# STM32_RX.net
KiCad netlist of a schematic drawn in EAGLE
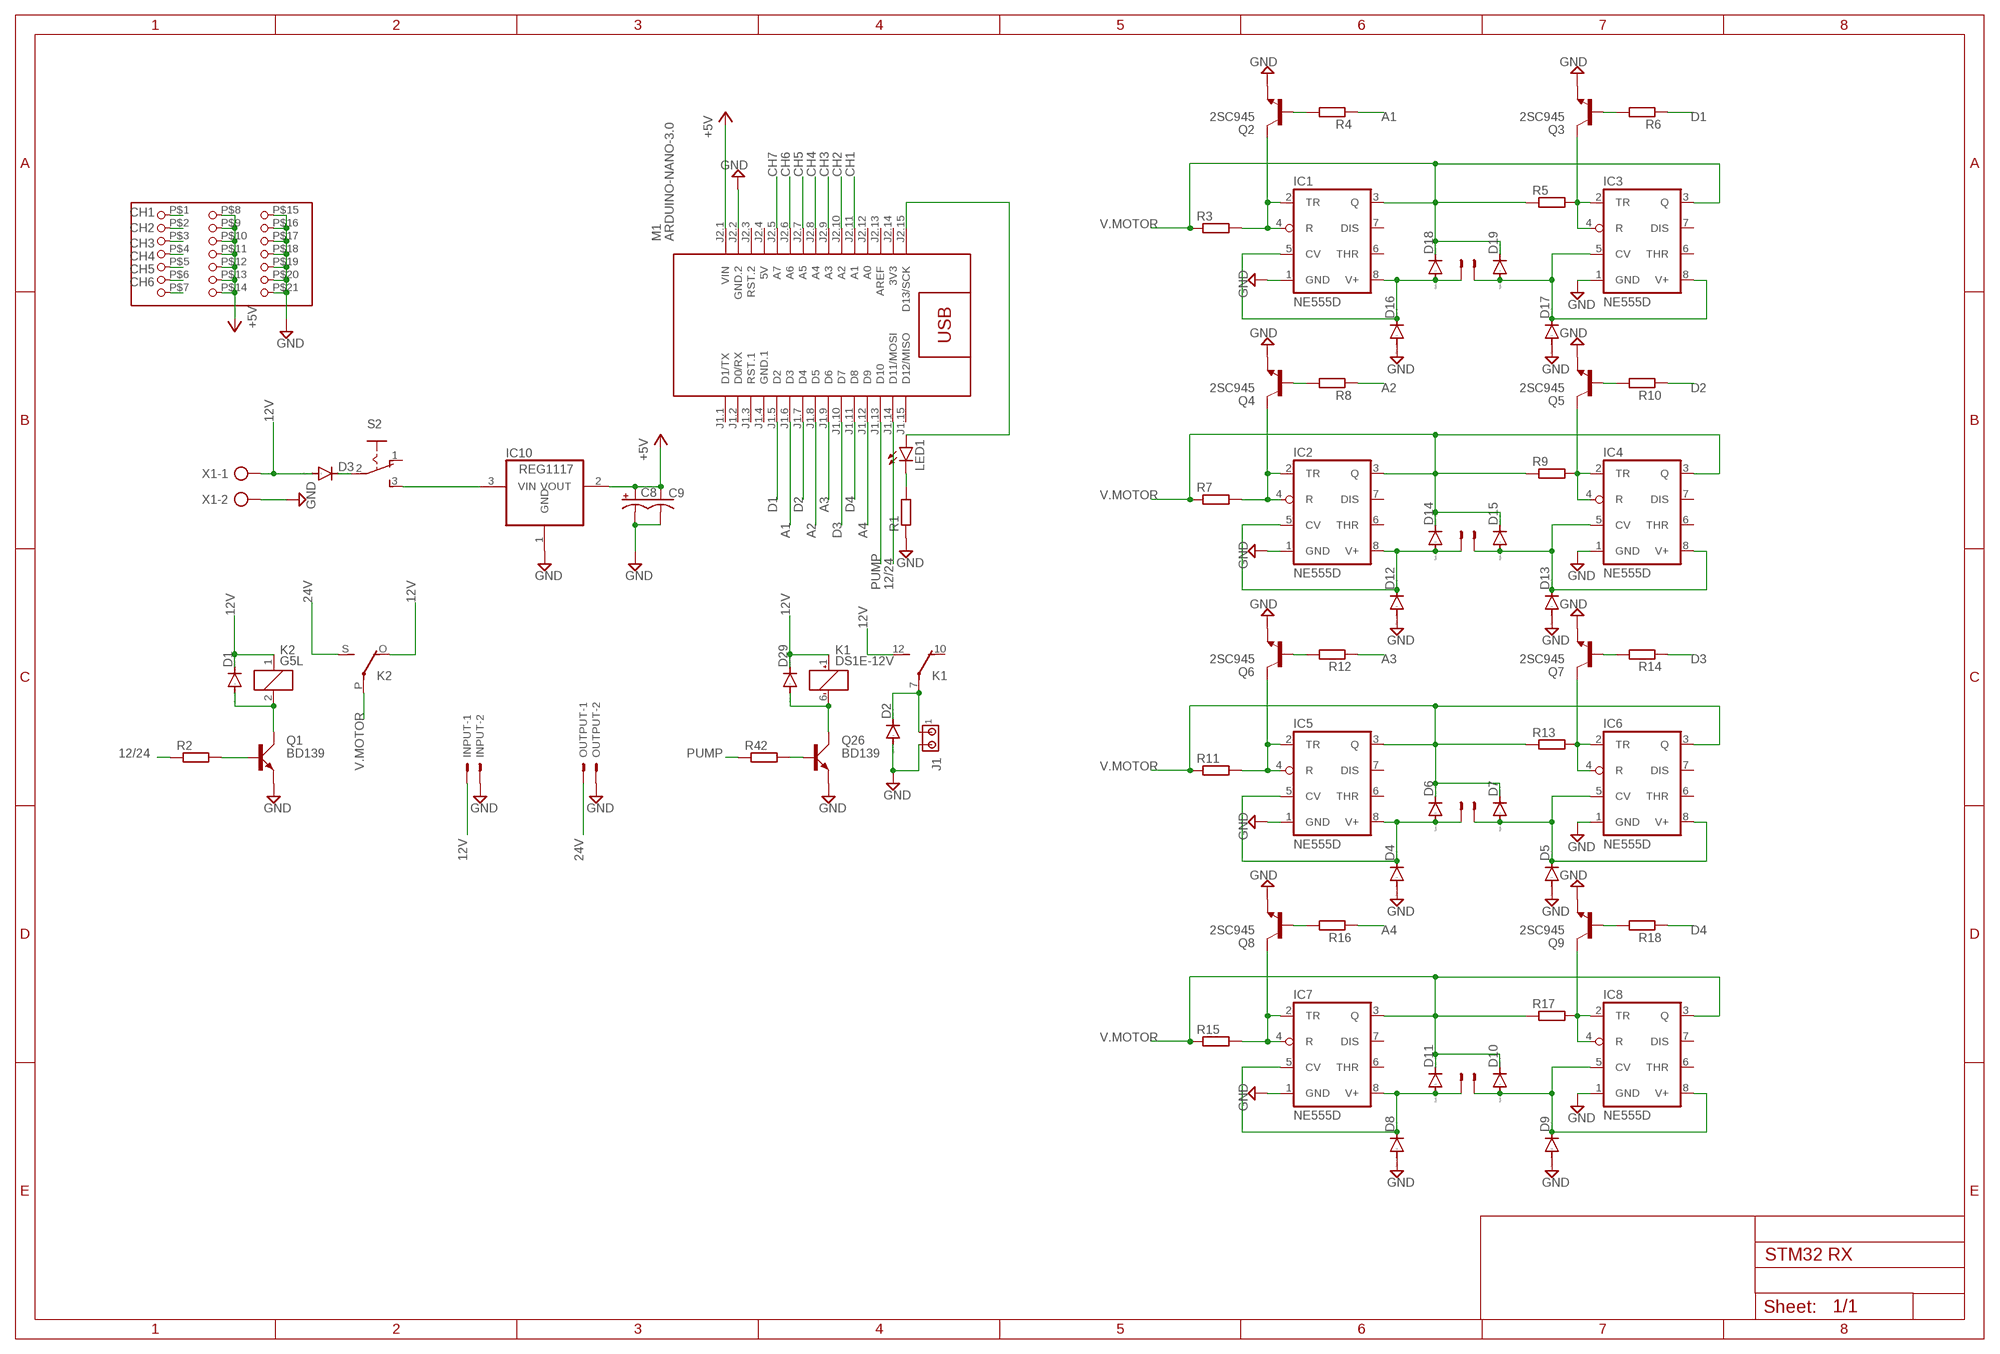
[diagram p0: schematic, sheet 1]

(export (version "E")
  (design (tool "Eeschema 10.0.6"))
  (components
    (comp (ref "C8")
      (value "CPOL-USE2.5-6")
      (footprint "eagle-import:E2,5-6")
      (libsource (lib "eagle-import") (part "CPOL-USE2.5-6"))
    )
    (comp (ref "C9")
      (value "C-US050-025X075")
      (footprint "eagle-import:C050-025X075")
      (libsource (lib "eagle-import") (part "C-US050-025X075"))
    )
    (comp (ref "D1")
      (value "1N4933")
      (footprint "eagle-import:DO41-10")
      (libsource (lib "eagle-import") (part "1N4933"))
    )
    (comp (ref "D2")
      (value "1N4933")
      (footprint "eagle-import:DO41-10")
      (libsource (lib "eagle-import") (part "1N4933"))
    )
    (comp (ref "D3")
      (value "1N4933")
      (footprint "eagle-import:DO41-10")
      (libsource (lib "eagle-import") (part "1N4933"))
    )
    (comp (ref "D4")
      (value "1N4933")
      (footprint "eagle-import:DO41-10")
      (libsource (lib "eagle-import") (part "1N4933"))
    )
    (comp (ref "D5")
      (value "1N4933")
      (footprint "eagle-import:DO41-10")
      (libsource (lib "eagle-import") (part "1N4933"))
    )
    (comp (ref "D6")
      (value "1N4933")
      (footprint "eagle-import:DO41-10")
      (libsource (lib "eagle-import") (part "1N4933"))
    )
    (comp (ref "D7")
      (value "1N4933")
      (footprint "eagle-import:DO41-10")
      (libsource (lib "eagle-import") (part "1N4933"))
    )
    (comp (ref "D8")
      (value "1N4933")
      (footprint "eagle-import:DO41-10")
      (libsource (lib "eagle-import") (part "1N4933"))
    )
    (comp (ref "D9")
      (value "1N4933")
      (footprint "eagle-import:DO41-10")
      (libsource (lib "eagle-import") (part "1N4933"))
    )
    (comp (ref "D10")
      (value "1N4933")
      (footprint "eagle-import:DO41-10")
      (libsource (lib "eagle-import") (part "1N4933"))
    )
    (comp (ref "D11")
      (value "1N4933")
      (footprint "eagle-import:DO41-10")
      (libsource (lib "eagle-import") (part "1N4933"))
    )
    (comp (ref "D12")
      (value "1N4933")
      (footprint "eagle-import:DO41-10")
      (libsource (lib "eagle-import") (part "1N4933"))
    )
    (comp (ref "D13")
      (value "1N4933")
      (footprint "eagle-import:DO41-10")
      (libsource (lib "eagle-import") (part "1N4933"))
    )
    (comp (ref "D14")
      (value "1N4933")
      (footprint "eagle-import:DO41-10")
      (libsource (lib "eagle-import") (part "1N4933"))
    )
    (comp (ref "D15")
      (value "1N4933")
      (footprint "eagle-import:DO41-10")
      (libsource (lib "eagle-import") (part "1N4933"))
    )
    (comp (ref "D16")
      (value "1N4933")
      (footprint "eagle-import:DO41-10")
      (libsource (lib "eagle-import") (part "1N4933"))
    )
    (comp (ref "D17")
      (value "1N4933")
      (footprint "eagle-import:DO41-10")
      (libsource (lib "eagle-import") (part "1N4933"))
    )
    (comp (ref "D18")
      (value "1N4933")
      (footprint "eagle-import:DO41-10")
      (libsource (lib "eagle-import") (part "1N4933"))
    )
    (comp (ref "D19")
      (value "1N4933")
      (footprint "eagle-import:DO41-10")
      (libsource (lib "eagle-import") (part "1N4933"))
    )
    (comp (ref "D29")
      (value "1N4933")
      (footprint "eagle-import:DO41-10")
      (libsource (lib "eagle-import") (part "1N4933"))
    )
    (comp (ref "IC1")
      (value "NE555D")
      (footprint "eagle-import:SO08")
      (libsource (lib "eagle-import") (part "555DNE"))
    )
    (comp (ref "IC2")
      (value "NE555D")
      (footprint "eagle-import:SO08")
      (libsource (lib "eagle-import") (part "555DNE"))
    )
    (comp (ref "IC3")
      (value "NE555D")
      (footprint "eagle-import:SO08")
      (libsource (lib "eagle-import") (part "555DNE"))
    )
    (comp (ref "IC4")
      (value "NE555D")
      (footprint "eagle-import:SO08")
      (libsource (lib "eagle-import") (part "555DNE"))
    )
    (comp (ref "IC5")
      (value "NE555D")
      (footprint "eagle-import:SO08")
      (libsource (lib "eagle-import") (part "555DNE"))
    )
    (comp (ref "IC6")
      (value "NE555D")
      (footprint "eagle-import:SO08")
      (libsource (lib "eagle-import") (part "555DNE"))
    )
    (comp (ref "IC7")
      (value "NE555D")
      (footprint "eagle-import:SO08")
      (libsource (lib "eagle-import") (part "555DNE"))
    )
    (comp (ref "IC8")
      (value "NE555D")
      (footprint "eagle-import:SO08")
      (libsource (lib "eagle-import") (part "555DNE"))
    )
    (comp (ref "IC10")
      (value "REG1117")
      (footprint "eagle-import:SOT223")
      (libsource (lib "eagle-import") (part "REG1117"))
    )
    (comp (ref "INPUT")
      (value "22-23-2021")
      (footprint "eagle-import:22-23-2021")
      (fields (field (name "MF") "MOLEX"))
      (libsource (lib "eagle-import") (part "22-23-2021"))
    )
    (comp (ref "J1")
      (value "MTA02-156")
      (footprint "eagle-import:1X2MTA")
      (libsource (lib "eagle-import") (part "MTA02-156"))
    )
    (comp (ref "K1")
      (value "DS1E-12V")
      (footprint "eagle-import:DS1E")
      (libsource (lib "eagle-import") (part "DS1E-?12V"))
    )
    (comp (ref "K2")
      (value "G5L")
      (footprint "eagle-import:G5LE")
      (libsource (lib "eagle-import") (part "G5L"))
    )
    (comp (ref "LED1")
      (value "LED5MM")
      (footprint "eagle-import:LED5MM")
      (libsource (lib "eagle-import") (part "LED5MM"))
    )
    (comp (ref "M1")
      (value "ARDUINO-NANO-3.0")
      (footprint "eagle-import:ARDUINO-NANO-3.0")
      (libsource (lib "eagle-import") (part "ARDUINO-NANO-3.0"))
    )
    (comp (ref "OUTPUT")
      (value "22-23-2021")
      (footprint "eagle-import:22-23-2021")
      (fields (field (name "MF") "MOLEX"))
      (libsource (lib "eagle-import") (part "22-23-2021"))
    )
    (comp (ref "OUTPUT1")
      (value "22-23-2021")
      (footprint "eagle-import:22-23-2021")
      (fields (field (name "MF") "MOLEX"))
      (libsource (lib "eagle-import") (part "22-23-2021"))
    )
    (comp (ref "OUTPUT2")
      (value "22-23-2021")
      (footprint "eagle-import:22-23-2021")
      (fields (field (name "MF") "MOLEX"))
      (libsource (lib "eagle-import") (part "22-23-2021"))
    )
    (comp (ref "OUTPUT3")
      (value "22-23-2021")
      (footprint "eagle-import:22-23-2021")
      (fields (field (name "MF") "MOLEX"))
      (libsource (lib "eagle-import") (part "22-23-2021"))
    )
    (comp (ref "OUTPUT4")
      (value "22-23-2021")
      (footprint "eagle-import:22-23-2021")
      (fields (field (name "MF") "MOLEX"))
      (libsource (lib "eagle-import") (part "22-23-2021"))
    )
    (comp (ref "Q1")
      (value "BD139")
      (footprint "eagle-import:TO126AV")
      (libsource (lib "eagle-import") (part "BD139"))
    )
    (comp (ref "Q2")
      (value "2SC945")
      (footprint "eagle-import:TO92-ECB")
      (libsource (lib "eagle-import") (part "2SC945"))
    )
    (comp (ref "Q3")
      (value "2SC945")
      (footprint "eagle-import:TO92-ECB")
      (libsource (lib "eagle-import") (part "2SC945"))
    )
    (comp (ref "Q4")
      (value "2SC945")
      (footprint "eagle-import:TO92-ECB")
      (libsource (lib "eagle-import") (part "2SC945"))
    )
    (comp (ref "Q5")
      (value "2SC945")
      (footprint "eagle-import:TO92-ECB")
      (libsource (lib "eagle-import") (part "2SC945"))
    )
    (comp (ref "Q6")
      (value "2SC945")
      (footprint "eagle-import:TO92-ECB")
      (libsource (lib "eagle-import") (part "2SC945"))
    )
    (comp (ref "Q7")
      (value "2SC945")
      (footprint "eagle-import:TO92-ECB")
      (libsource (lib "eagle-import") (part "2SC945"))
    )
    (comp (ref "Q8")
      (value "2SC945")
      (footprint "eagle-import:TO92-ECB")
      (libsource (lib "eagle-import") (part "2SC945"))
    )
    (comp (ref "Q9")
      (value "2SC945")
      (footprint "eagle-import:TO92-ECB")
      (libsource (lib "eagle-import") (part "2SC945"))
    )
    (comp (ref "Q26")
      (value "BD139")
      (footprint "eagle-import:TO126AV")
      (libsource (lib "eagle-import") (part "BD139"))
    )
    (comp (ref "R1")
      (value "R-EU_0207/10")
      (footprint "eagle-import:0207_10")
      (libsource (lib "eagle-import") (part "R-EU_0207/10"))
    )
    (comp (ref "R2")
      (value "R-EU_0207/10")
      (footprint "eagle-import:0207_10")
      (libsource (lib "eagle-import") (part "R-EU_0207/10"))
    )
    (comp (ref "R3")
      (value "R-EU_0207/10")
      (footprint "eagle-import:0207_10")
      (libsource (lib "eagle-import") (part "R-EU_0207/10"))
    )
    (comp (ref "R4")
      (value "R-EU_0207/10")
      (footprint "eagle-import:0207_10")
      (libsource (lib "eagle-import") (part "R-EU_0207/10"))
    )
    (comp (ref "R5")
      (value "R-EU_0207/10")
      (footprint "eagle-import:0207_10")
      (libsource (lib "eagle-import") (part "R-EU_0207/10"))
    )
    (comp (ref "R6")
      (value "R-EU_0207/10")
      (footprint "eagle-import:0207_10")
      (libsource (lib "eagle-import") (part "R-EU_0207/10"))
    )
    (comp (ref "R7")
      (value "R-EU_0207/10")
      (footprint "eagle-import:0207_10")
      (libsource (lib "eagle-import") (part "R-EU_0207/10"))
    )
    (comp (ref "R8")
      (value "R-EU_0207/10")
      (footprint "eagle-import:0207_10")
      (libsource (lib "eagle-import") (part "R-EU_0207/10"))
    )
    (comp (ref "R9")
      (value "R-EU_0207/10")
      (footprint "eagle-import:0207_10")
      (libsource (lib "eagle-import") (part "R-EU_0207/10"))
    )
    (comp (ref "R10")
      (value "R-EU_0207/10")
      (footprint "eagle-import:0207_10")
      (libsource (lib "eagle-import") (part "R-EU_0207/10"))
    )
    (comp (ref "R11")
      (value "R-EU_0207/10")
      (footprint "eagle-import:0207_10")
      (libsource (lib "eagle-import") (part "R-EU_0207/10"))
    )
    (comp (ref "R12")
      (value "R-EU_0207/10")
      (footprint "eagle-import:0207_10")
      (libsource (lib "eagle-import") (part "R-EU_0207/10"))
    )
    (comp (ref "R13")
      (value "R-EU_0207/10")
      (footprint "eagle-import:0207_10")
      (libsource (lib "eagle-import") (part "R-EU_0207/10"))
    )
    (comp (ref "R14")
      (value "R-EU_0207/10")
      (footprint "eagle-import:0207_10")
      (libsource (lib "eagle-import") (part "R-EU_0207/10"))
    )
    (comp (ref "R15")
      (value "R-EU_0207/10")
      (footprint "eagle-import:0207_10")
      (libsource (lib "eagle-import") (part "R-EU_0207/10"))
    )
    (comp (ref "R16")
      (value "R-EU_0207/10")
      (footprint "eagle-import:0207_10")
      (libsource (lib "eagle-import") (part "R-EU_0207/10"))
    )
    (comp (ref "R17")
      (value "R-EU_0207/10")
      (footprint "eagle-import:0207_10")
      (libsource (lib "eagle-import") (part "R-EU_0207/10"))
    )
    (comp (ref "R18")
      (value "R-EU_0207/10")
      (footprint "eagle-import:0207_10")
      (libsource (lib "eagle-import") (part "R-EU_0207/10"))
    )
    (comp (ref "R42")
      (value "R-EU_0207/10")
      (footprint "eagle-import:0207_10")
      (libsource (lib "eagle-import") (part "R-EU_0207/10"))
    )
    (comp (ref "S2")
      (value "255SB")
      (footprint "eagle-import:255SB")
      (libsource (lib "eagle-import") (part "255SB"))
    )
    (comp (ref "U$1")
      (value "PINHEAD3")
      (footprint "eagle-import:PINHEAD3")
      (libsource (lib "eagle-import") (part "PINHEAD3"))
    )
    (comp (ref "X1")
      (value "AK500/2")
      (footprint "eagle-import:AK500_2")
      (libsource (lib "eagle-import") (part "AK500/2"))
    )
  )
  (nets
    (net (code "1") (name "+5V") (class "Default")
      (node (ref "C8") (pin "+") (pinfunction "+_+") (pintype "passive"))
      (node (ref "C9") (pin "1") (pinfunction "1_1") (pintype "passive"))
      (node (ref "IC10") (pin "2") (pinfunction "VOUT_2") (pintype "output"))
      (node (ref "M1") (pin "J2.1") (pinfunction "VIN_J2.1") (pintype "power_in"))
      (node (ref "U$1") (pin "P$10") (pinfunction "P$10_P$10") (pintype "bidirectional"))
      (node (ref "U$1") (pin "P$11") (pinfunction "P$11_P$11") (pintype "bidirectional"))
      (node (ref "U$1") (pin "P$12") (pinfunction "P$12_P$12") (pintype "bidirectional"))
      (node (ref "U$1") (pin "P$13") (pinfunction "P$13_P$13") (pintype "bidirectional"))
      (node (ref "U$1") (pin "P$14") (pinfunction "P$14_P$14") (pintype "bidirectional"))
      (node (ref "U$1") (pin "P$8") (pinfunction "P$8_P$8") (pintype "bidirectional"))
      (node (ref "U$1") (pin "P$9") (pinfunction "P$9_P$9") (pintype "bidirectional"))
    )
    (net (code "2") (name "/3V3") (class "Default")
      (node (ref "M1") (pin "J2.14") (pinfunction "3V3_J2.14") (pintype "power_in"))
    )
    (net (code "3") (name "/5V") (class "Default")
      (node (ref "M1") (pin "J2.4") (pinfunction "5V_J2.4") (pintype "power_in"))
    )
    (net (code "4") (name "/12V") (class "Default")
      (node (ref "D1") (pin "C") (pinfunction "C_C") (pintype "passive"))
      (node (ref "D29") (pin "C") (pinfunction "C_C") (pintype "passive"))
      (node (ref "D3") (pin "A") (pinfunction "A_A") (pintype "passive"))
      (node (ref "INPUT") (pin "1") (pinfunction "S_1") (pintype "passive"))
      (node (ref "K1") (pin "1") (pinfunction "+_1") (pintype "passive"))
      (node (ref "K1") (pin "12") (pinfunction "S_12") (pintype "passive"))
      (node (ref "K2") (pin "1") (pinfunction "1_1") (pintype "passive"))
      (node (ref "K2") (pin "O") (pinfunction "O_O") (pintype "passive"))
      (node (ref "X1") (pin "1") (pinfunction "KL_1") (pintype "passive"))
    )
    (net (code "5") (name "/12{slash}24") (class "Default")
      (node (ref "M1") (pin "J1.14") (pinfunction "D11/MOSI_J1.14") (pintype "bidirectional"))
      (node (ref "R2") (pin "1") (pinfunction "1_1") (pintype "passive"))
    )
    (net (code "6") (name "/24V") (class "Default")
      (node (ref "K2") (pin "S") (pinfunction "S_S") (pintype "passive"))
      (node (ref "OUTPUT") (pin "1") (pinfunction "S_1") (pintype "passive"))
    )
    (net (code "7") (name "/A1") (class "Default")
      (node (ref "M1") (pin "J1.6") (pinfunction "D3_J1.6") (pintype "bidirectional"))
      (node (ref "R4") (pin "1") (pinfunction "1_1") (pintype "passive"))
    )
    (net (code "8") (name "/A2") (class "Default")
      (node (ref "M1") (pin "J1.8") (pinfunction "D5_J1.8") (pintype "bidirectional"))
      (node (ref "R8") (pin "1") (pinfunction "1_1") (pintype "passive"))
    )
    (net (code "9") (name "/A3") (class "Default")
      (node (ref "M1") (pin "J1.9") (pinfunction "D6_J1.9") (pintype "bidirectional"))
      (node (ref "R12") (pin "1") (pinfunction "1_1") (pintype "passive"))
    )
    (net (code "10") (name "/A4") (class "Default")
      (node (ref "M1") (pin "J1.12") (pinfunction "D9_J1.12") (pintype "bidirectional"))
      (node (ref "R16") (pin "1") (pinfunction "1_1") (pintype "passive"))
    )
    (net (code "11") (name "/CH1") (class "Default")
      (node (ref "M1") (pin "J2.11") (pinfunction "A1_J2.11") (pintype "bidirectional"))
      (node (ref "U$1") (pin "P$1") (pinfunction "P$1_P$1") (pintype "bidirectional"))
    )
    (net (code "12") (name "/CH2") (class "Default")
      (node (ref "M1") (pin "J2.10") (pinfunction "A2_J2.10") (pintype "bidirectional"))
      (node (ref "U$1") (pin "P$2") (pinfunction "P$2_P$2") (pintype "bidirectional"))
    )
    (net (code "13") (name "/CH3") (class "Default")
      (node (ref "M1") (pin "J2.9") (pinfunction "A3_J2.9") (pintype "bidirectional"))
      (node (ref "U$1") (pin "P$3") (pinfunction "P$3_P$3") (pintype "bidirectional"))
    )
    (net (code "14") (name "/CH4") (class "Default")
      (node (ref "M1") (pin "J2.8") (pinfunction "A4_J2.8") (pintype "bidirectional"))
      (node (ref "U$1") (pin "P$4") (pinfunction "P$4_P$4") (pintype "bidirectional"))
    )
    (net (code "15") (name "/CH5") (class "Default")
      (node (ref "M1") (pin "J2.7") (pinfunction "A5_J2.7") (pintype "bidirectional"))
      (node (ref "U$1") (pin "P$5") (pinfunction "P$5_P$5") (pintype "bidirectional"))
    )
    (net (code "16") (name "/CH6") (class "Default")
      (node (ref "M1") (pin "J2.6") (pinfunction "A6_J2.6") (pintype "bidirectional"))
      (node (ref "U$1") (pin "P$6") (pinfunction "P$6_P$6") (pintype "bidirectional"))
    )
    (net (code "17") (name "/CH7") (class "Default")
      (node (ref "M1") (pin "J2.5") (pinfunction "A7_J2.5") (pintype "bidirectional"))
    )
    (net (code "18") (name "/D1") (class "Default")
      (node (ref "M1") (pin "J1.5") (pinfunction "D2_J1.5") (pintype "bidirectional"))
      (node (ref "R6") (pin "1") (pinfunction "1_1") (pintype "passive"))
    )
    (net (code "19") (name "/D2") (class "Default")
      (node (ref "M1") (pin "J1.7") (pinfunction "D4_J1.7") (pintype "bidirectional"))
      (node (ref "R10") (pin "1") (pinfunction "1_1") (pintype "passive"))
    )
    (net (code "20") (name "/D3") (class "Default")
      (node (ref "M1") (pin "J1.10") (pinfunction "D7_J1.10") (pintype "bidirectional"))
      (node (ref "R14") (pin "1") (pinfunction "1_1") (pintype "passive"))
    )
    (net (code "21") (name "/D4") (class "Default")
      (node (ref "M1") (pin "J1.11") (pinfunction "D8_J1.11") (pintype "bidirectional"))
      (node (ref "R18") (pin "1") (pinfunction "1_1") (pintype "passive"))
    )
    (net (code "22") (name "/GND.1") (class "Default")
      (node (ref "M1") (pin "J1.4") (pinfunction "GND.1_J1.4") (pintype "power_in"))
    )
    (net (code "23") (name "/PUMP") (class "Default")
      (node (ref "M1") (pin "J1.13") (pinfunction "D10_J1.13") (pintype "bidirectional"))
      (node (ref "R42") (pin "1") (pinfunction "1_1") (pintype "passive"))
    )
    (net (code "24") (name "/V.MOTOR") (class "Default")
      (node (ref "D10") (pin "C") (pinfunction "C_C") (pintype "passive"))
      (node (ref "D11") (pin "C") (pinfunction "C_C") (pintype "passive"))
      (node (ref "D14") (pin "C") (pinfunction "C_C") (pintype "passive"))
      (node (ref "D15") (pin "C") (pinfunction "C_C") (pintype "passive"))
      (node (ref "D18") (pin "C") (pinfunction "C_C") (pintype "passive"))
      (node (ref "D19") (pin "C") (pinfunction "C_C") (pintype "passive"))
      (node (ref "D6") (pin "C") (pinfunction "C_C") (pintype "passive"))
      (node (ref "D7") (pin "C") (pinfunction "C_C") (pintype "passive"))
      (node (ref "IC1") (pin "3") (pinfunction "Q_3") (pintype "output"))
      (node (ref "IC2") (pin "3") (pinfunction "Q_3") (pintype "output"))
      (node (ref "IC3") (pin "3") (pinfunction "Q_3") (pintype "output"))
      (node (ref "IC4") (pin "3") (pinfunction "Q_3") (pintype "output"))
      (node (ref "IC5") (pin "3") (pinfunction "Q_3") (pintype "output"))
      (node (ref "IC6") (pin "3") (pinfunction "Q_3") (pintype "output"))
      (node (ref "IC7") (pin "3") (pinfunction "Q_3") (pintype "output"))
      (node (ref "IC8") (pin "3") (pinfunction "Q_3") (pintype "output"))
      (node (ref "K2") (pin "P") (pinfunction "P_P") (pintype "passive"))
      (node (ref "R11") (pin "1") (pinfunction "1_1") (pintype "passive"))
      (node (ref "R13") (pin "1") (pinfunction "1_1") (pintype "passive"))
      (node (ref "R15") (pin "1") (pinfunction "1_1") (pintype "passive"))
      (node (ref "R17") (pin "1") (pinfunction "1_1") (pintype "passive"))
      (node (ref "R3") (pin "1") (pinfunction "1_1") (pintype "passive"))
      (node (ref "R5") (pin "1") (pinfunction "1_1") (pintype "passive"))
      (node (ref "R7") (pin "1") (pinfunction "1_1") (pintype "passive"))
      (node (ref "R9") (pin "1") (pinfunction "1_1") (pintype "passive"))
    )
    (net (code "25") (name "GND") (class "Default")
      (node (ref "C8") (pin "-") (pinfunction "-_-") (pintype "passive"))
      (node (ref "C9") (pin "2") (pinfunction "2_2") (pintype "passive"))
      (node (ref "D12") (pin "A") (pinfunction "A_A") (pintype "passive"))
      (node (ref "D13") (pin "A") (pinfunction "A_A") (pintype "passive"))
      (node (ref "D16") (pin "A") (pinfunction "A_A") (pintype "passive"))
      (node (ref "D17") (pin "A") (pinfunction "A_A") (pintype "passive"))
      (node (ref "D2") (pin "A") (pinfunction "A_A") (pintype "passive"))
      (node (ref "D4") (pin "A") (pinfunction "A_A") (pintype "passive"))
      (node (ref "D5") (pin "A") (pinfunction "A_A") (pintype "passive"))
      (node (ref "D8") (pin "A") (pinfunction "A_A") (pintype "passive"))
      (node (ref "D9") (pin "A") (pinfunction "A_A") (pintype "passive"))
      (node (ref "IC1") (pin "1") (pinfunction "GND_1") (pintype "power_in"))
      (node (ref "IC10") (pin "1") (pinfunction "GND_1") (pintype "power_in"))
      (node (ref "IC2") (pin "1") (pinfunction "GND_1") (pintype "power_in"))
      (node (ref "IC3") (pin "1") (pinfunction "GND_1") (pintype "power_in"))
      (node (ref "IC4") (pin "1") (pinfunction "GND_1") (pintype "power_in"))
      (node (ref "IC5") (pin "1") (pinfunction "GND_1") (pintype "power_in"))
      (node (ref "IC6") (pin "1") (pinfunction "GND_1") (pintype "power_in"))
      (node (ref "IC7") (pin "1") (pinfunction "GND_1") (pintype "power_in"))
      (node (ref "IC8") (pin "1") (pinfunction "GND_1") (pintype "power_in"))
      (node (ref "INPUT") (pin "2") (pinfunction "S_2") (pintype "passive"))
      (node (ref "J1") (pin "2") (pinfunction "2_2") (pintype "passive"))
      (node (ref "M1") (pin "J2.2") (pinfunction "GND.2_J2.2") (pintype "power_in"))
      (node (ref "OUTPUT") (pin "2") (pinfunction "S_2") (pintype "passive"))
      (node (ref "Q1") (pin "E") (pinfunction "E_E") (pintype "passive"))
      (node (ref "Q2") (pin "E") (pinfunction "E_E") (pintype "passive"))
      (node (ref "Q26") (pin "E") (pinfunction "E_E") (pintype "passive"))
      (node (ref "Q3") (pin "E") (pinfunction "E_E") (pintype "passive"))
      (node (ref "Q4") (pin "E") (pinfunction "E_E") (pintype "passive"))
      (node (ref "Q5") (pin "E") (pinfunction "E_E") (pintype "passive"))
      (node (ref "Q6") (pin "E") (pinfunction "E_E") (pintype "passive"))
      (node (ref "Q7") (pin "E") (pinfunction "E_E") (pintype "passive"))
      (node (ref "Q8") (pin "E") (pinfunction "E_E") (pintype "passive"))
      (node (ref "Q9") (pin "E") (pinfunction "E_E") (pintype "passive"))
      (node (ref "R1") (pin "1") (pinfunction "1_1") (pintype "passive"))
      (node (ref "U$1") (pin "P$15") (pinfunction "P$15_P$15") (pintype "bidirectional"))
      (node (ref "U$1") (pin "P$16") (pinfunction "P$16_P$16") (pintype "bidirectional"))
      (node (ref "U$1") (pin "P$17") (pinfunction "P$17_P$17") (pintype "bidirectional"))
      (node (ref "U$1") (pin "P$18") (pinfunction "P$18_P$18") (pintype "bidirectional"))
      (node (ref "U$1") (pin "P$19") (pinfunction "P$19_P$19") (pintype "bidirectional"))
      (node (ref "U$1") (pin "P$20") (pinfunction "P$20_P$20") (pintype "bidirectional"))
      (node (ref "U$1") (pin "P$21") (pinfunction "P$21_P$21") (pintype "bidirectional"))
      (node (ref "X1") (pin "2") (pinfunction "KL_2") (pintype "passive"))
    )
    (net (code "26") (name "Net-(D1-PadA)") (class "Default")
      (node (ref "D1") (pin "A") (pinfunction "A_A") (pintype "passive"))
      (node (ref "K2") (pin "2") (pinfunction "2_2") (pintype "passive"))
      (node (ref "Q1") (pin "C") (pinfunction "C_C") (pintype "passive"))
    )
    (net (code "27") (name "Net-(IC1-CV)") (class "Default")
      (node (ref "D16") (pin "C") (pinfunction "C_C") (pintype "passive"))
      (node (ref "D18") (pin "A") (pinfunction "A_A") (pintype "passive"))
      (node (ref "IC1") (pin "5") (pinfunction "CV_5") (pintype "input"))
      (node (ref "IC1") (pin "8") (pinfunction "V+_8") (pintype "power_in"))
      (node (ref "OUTPUT1") (pin "1") (pinfunction "S_1") (pintype "passive"))
    )
    (net (code "28") (name "Net-(IC1-R)") (class "Default")
      (node (ref "IC1") (pin "2") (pinfunction "TR_2") (pintype "input"))
      (node (ref "IC1") (pin "4") (pinfunction "R_4") (pintype "input"))
      (node (ref "Q2") (pin "C") (pinfunction "C_C") (pintype "passive"))
      (node (ref "R3") (pin "2") (pinfunction "2_2") (pintype "passive"))
    )
    (net (code "29") (name "Net-(IC2-CV)") (class "Default")
      (node (ref "D12") (pin "C") (pinfunction "C_C") (pintype "passive"))
      (node (ref "D14") (pin "A") (pinfunction "A_A") (pintype "passive"))
      (node (ref "IC2") (pin "5") (pinfunction "CV_5") (pintype "input"))
      (node (ref "IC2") (pin "8") (pinfunction "V+_8") (pintype "power_in"))
      (node (ref "OUTPUT2") (pin "1") (pinfunction "S_1") (pintype "passive"))
    )
    (net (code "30") (name "Net-(IC2-R)") (class "Default")
      (node (ref "IC2") (pin "2") (pinfunction "TR_2") (pintype "input"))
      (node (ref "IC2") (pin "4") (pinfunction "R_4") (pintype "input"))
      (node (ref "Q4") (pin "C") (pinfunction "C_C") (pintype "passive"))
      (node (ref "R7") (pin "2") (pinfunction "2_2") (pintype "passive"))
    )
    (net (code "31") (name "Net-(IC3-CV)") (class "Default")
      (node (ref "D17") (pin "C") (pinfunction "C_C") (pintype "passive"))
      (node (ref "D19") (pin "A") (pinfunction "A_A") (pintype "passive"))
      (node (ref "IC3") (pin "5") (pinfunction "CV_5") (pintype "input"))
      (node (ref "IC3") (pin "8") (pinfunction "V+_8") (pintype "power_in"))
      (node (ref "OUTPUT1") (pin "2") (pinfunction "S_2") (pintype "passive"))
    )
    (net (code "32") (name "Net-(IC3-R)") (class "Default")
      (node (ref "IC3") (pin "2") (pinfunction "TR_2") (pintype "input"))
      (node (ref "IC3") (pin "4") (pinfunction "R_4") (pintype "input"))
      (node (ref "Q3") (pin "C") (pinfunction "C_C") (pintype "passive"))
      (node (ref "R5") (pin "2") (pinfunction "2_2") (pintype "passive"))
    )
    (net (code "33") (name "Net-(IC4-CV)") (class "Default")
      (node (ref "D13") (pin "C") (pinfunction "C_C") (pintype "passive"))
      (node (ref "D15") (pin "A") (pinfunction "A_A") (pintype "passive"))
      (node (ref "IC4") (pin "5") (pinfunction "CV_5") (pintype "input"))
      (node (ref "IC4") (pin "8") (pinfunction "V+_8") (pintype "power_in"))
      (node (ref "OUTPUT2") (pin "2") (pinfunction "S_2") (pintype "passive"))
    )
    (net (code "34") (name "Net-(IC4-R)") (class "Default")
      (node (ref "IC4") (pin "2") (pinfunction "TR_2") (pintype "input"))
      (node (ref "IC4") (pin "4") (pinfunction "R_4") (pintype "input"))
      (node (ref "Q5") (pin "C") (pinfunction "C_C") (pintype "passive"))
      (node (ref "R9") (pin "2") (pinfunction "2_2") (pintype "passive"))
    )
    (net (code "35") (name "Net-(IC5-CV)") (class "Default")
      (node (ref "D4") (pin "C") (pinfunction "C_C") (pintype "passive"))
      (node (ref "D6") (pin "A") (pinfunction "A_A") (pintype "passive"))
      (node (ref "IC5") (pin "5") (pinfunction "CV_5") (pintype "input"))
      (node (ref "IC5") (pin "8") (pinfunction "V+_8") (pintype "power_in"))
      (node (ref "OUTPUT3") (pin "1") (pinfunction "S_1") (pintype "passive"))
    )
    (net (code "36") (name "Net-(IC5-R)") (class "Default")
      (node (ref "IC5") (pin "2") (pinfunction "TR_2") (pintype "input"))
      (node (ref "IC5") (pin "4") (pinfunction "R_4") (pintype "input"))
      (node (ref "Q6") (pin "C") (pinfunction "C_C") (pintype "passive"))
      (node (ref "R11") (pin "2") (pinfunction "2_2") (pintype "passive"))
    )
    (net (code "37") (name "Net-(IC6-CV)") (class "Default")
      (node (ref "D5") (pin "C") (pinfunction "C_C") (pintype "passive"))
      (node (ref "D7") (pin "A") (pinfunction "A_A") (pintype "passive"))
      (node (ref "IC6") (pin "5") (pinfunction "CV_5") (pintype "input"))
      (node (ref "IC6") (pin "8") (pinfunction "V+_8") (pintype "power_in"))
      (node (ref "OUTPUT3") (pin "2") (pinfunction "S_2") (pintype "passive"))
    )
    (net (code "38") (name "Net-(IC6-R)") (class "Default")
      (node (ref "IC6") (pin "2") (pinfunction "TR_2") (pintype "input"))
      (node (ref "IC6") (pin "4") (pinfunction "R_4") (pintype "input"))
      (node (ref "Q7") (pin "C") (pinfunction "C_C") (pintype "passive"))
      (node (ref "R13") (pin "2") (pinfunction "2_2") (pintype "passive"))
    )
    (net (code "39") (name "Net-(IC7-CV)") (class "Default")
      (node (ref "D11") (pin "A") (pinfunction "A_A") (pintype "passive"))
      (node (ref "D8") (pin "C") (pinfunction "C_C") (pintype "passive"))
      (node (ref "IC7") (pin "5") (pinfunction "CV_5") (pintype "input"))
      (node (ref "IC7") (pin "8") (pinfunction "V+_8") (pintype "power_in"))
      (node (ref "OUTPUT4") (pin "1") (pinfunction "S_1") (pintype "passive"))
    )
    (net (code "40") (name "Net-(IC7-R)") (class "Default")
      (node (ref "IC7") (pin "2") (pinfunction "TR_2") (pintype "input"))
      (node (ref "IC7") (pin "4") (pinfunction "R_4") (pintype "input"))
      (node (ref "Q8") (pin "C") (pinfunction "C_C") (pintype "passive"))
      (node (ref "R15") (pin "2") (pinfunction "2_2") (pintype "passive"))
    )
    (net (code "41") (name "Net-(IC8-CV)") (class "Default")
      (node (ref "D10") (pin "A") (pinfunction "A_A") (pintype "passive"))
      (node (ref "D9") (pin "C") (pinfunction "C_C") (pintype "passive"))
      (node (ref "IC8") (pin "5") (pinfunction "CV_5") (pintype "input"))
      (node (ref "IC8") (pin "8") (pinfunction "V+_8") (pintype "power_in"))
      (node (ref "OUTPUT4") (pin "2") (pinfunction "S_2") (pintype "passive"))
    )
    (net (code "42") (name "Net-(IC8-R)") (class "Default")
      (node (ref "IC8") (pin "2") (pinfunction "TR_2") (pintype "input"))
      (node (ref "IC8") (pin "4") (pinfunction "R_4") (pintype "input"))
      (node (ref "Q9") (pin "C") (pinfunction "C_C") (pintype "passive"))
      (node (ref "R17") (pin "2") (pinfunction "2_2") (pintype "passive"))
    )
    (net (code "43") (name "Net-(IC10-VIN)") (class "Default")
      (node (ref "IC10") (pin "3") (pinfunction "VIN_3") (pintype "input"))
      (node (ref "S2") (pin "3") (pinfunction "S_3") (pintype "passive"))
    )
    (net (code "44") (name "Net-(K1A--)") (class "Default")
      (node (ref "D29") (pin "A") (pinfunction "A_A") (pintype "passive"))
      (node (ref "K1") (pin "6") (pinfunction "-_6") (pintype "passive"))
      (node (ref "Q26") (pin "C") (pinfunction "C_C") (pintype "passive"))
    )
    (net (code "45") (name "Net-(K1B-P)") (class "Default")
      (node (ref "D2") (pin "C") (pinfunction "C_C") (pintype "passive"))
      (node (ref "J1") (pin "1") (pinfunction "1_1") (pintype "passive"))
      (node (ref "K1") (pin "7") (pinfunction "P_7") (pintype "passive"))
    )
    (net (code "46") (name "Net-(LED1-C)") (class "Default")
      (node (ref "LED1") (pin "K") (pinfunction "C_K") (pintype "passive"))
      (node (ref "R1") (pin "2") (pinfunction "2_2") (pintype "passive"))
    )
    (net (code "47") (name "Net-(M1-D13{slash}SCK)") (class "Default")
      (node (ref "LED1") (pin "A") (pinfunction "A_A") (pintype "passive"))
      (node (ref "M1") (pin "J2.15") (pinfunction "D13/SCK_J2.15") (pintype "bidirectional"))
    )
    (net (code "48") (name "Net-(Q1-PadB)") (class "Default")
      (node (ref "Q1") (pin "B") (pinfunction "B_B") (pintype "passive"))
      (node (ref "R2") (pin "2") (pinfunction "2_2") (pintype "passive"))
    )
    (net (code "49") (name "Net-(Q2-PadB)") (class "Default")
      (node (ref "Q2") (pin "B") (pinfunction "B_B") (pintype "passive"))
      (node (ref "R4") (pin "2") (pinfunction "2_2") (pintype "passive"))
    )
    (net (code "50") (name "Net-(Q3-PadB)") (class "Default")
      (node (ref "Q3") (pin "B") (pinfunction "B_B") (pintype "passive"))
      (node (ref "R6") (pin "2") (pinfunction "2_2") (pintype "passive"))
    )
    (net (code "51") (name "Net-(Q4-PadB)") (class "Default")
      (node (ref "Q4") (pin "B") (pinfunction "B_B") (pintype "passive"))
      (node (ref "R8") (pin "2") (pinfunction "2_2") (pintype "passive"))
    )
    (net (code "52") (name "Net-(Q5-PadB)") (class "Default")
      (node (ref "Q5") (pin "B") (pinfunction "B_B") (pintype "passive"))
      (node (ref "R10") (pin "2") (pinfunction "2_2") (pintype "passive"))
    )
    (net (code "53") (name "Net-(Q6-PadB)") (class "Default")
      (node (ref "Q6") (pin "B") (pinfunction "B_B") (pintype "passive"))
      (node (ref "R12") (pin "2") (pinfunction "2_2") (pintype "passive"))
    )
    (net (code "54") (name "Net-(Q7-PadB)") (class "Default")
      (node (ref "Q7") (pin "B") (pinfunction "B_B") (pintype "passive"))
      (node (ref "R14") (pin "2") (pinfunction "2_2") (pintype "passive"))
    )
    (net (code "55") (name "Net-(Q8-PadB)") (class "Default")
      (node (ref "Q8") (pin "B") (pinfunction "B_B") (pintype "passive"))
      (node (ref "R16") (pin "2") (pinfunction "2_2") (pintype "passive"))
    )
    (net (code "56") (name "Net-(Q9-PadB)") (class "Default")
      (node (ref "Q9") (pin "B") (pinfunction "B_B") (pintype "passive"))
      (node (ref "R18") (pin "2") (pinfunction "2_2") (pintype "passive"))
    )
    (net (code "57") (name "Net-(Q26-PadB)") (class "Default")
      (node (ref "Q26") (pin "B") (pinfunction "B_B") (pintype "passive"))
      (node (ref "R42") (pin "2") (pinfunction "2_2") (pintype "passive"))
    )
    (net (code "58") (name "Net-(S2-P)") (class "Default")
      (node (ref "D3") (pin "C") (pinfunction "C_C") (pintype "passive"))
      (node (ref "S2") (pin "2") (pinfunction "P_2") (pintype "passive"))
    )
    (net (code "59") (name "unconnected-(IC1-DIS-Pad7)") (class "Default")
      (node (ref "IC1") (pin "7") (pinfunction "DIS_7") (pintype "input"))
    )
    (net (code "60") (name "unconnected-(IC1-THR-Pad6)") (class "Default")
      (node (ref "IC1") (pin "6") (pinfunction "THR_6") (pintype "input"))
    )
    (net (code "61") (name "unconnected-(IC2-DIS-Pad7)") (class "Default")
      (node (ref "IC2") (pin "7") (pinfunction "DIS_7") (pintype "input"))
    )
    (net (code "62") (name "unconnected-(IC2-THR-Pad6)") (class "Default")
      (node (ref "IC2") (pin "6") (pinfunction "THR_6") (pintype "input"))
    )
    (net (code "63") (name "unconnected-(IC3-DIS-Pad7)") (class "Default")
      (node (ref "IC3") (pin "7") (pinfunction "DIS_7") (pintype "input"))
    )
    (net (code "64") (name "unconnected-(IC3-THR-Pad6)") (class "Default")
      (node (ref "IC3") (pin "6") (pinfunction "THR_6") (pintype "input"))
    )
    (net (code "65") (name "unconnected-(IC4-DIS-Pad7)") (class "Default")
      (node (ref "IC4") (pin "7") (pinfunction "DIS_7") (pintype "input"))
    )
    (net (code "66") (name "unconnected-(IC4-THR-Pad6)") (class "Default")
      (node (ref "IC4") (pin "6") (pinfunction "THR_6") (pintype "input"))
    )
    (net (code "67") (name "unconnected-(IC5-DIS-Pad7)") (class "Default")
      (node (ref "IC5") (pin "7") (pinfunction "DIS_7") (pintype "input"))
    )
    (net (code "68") (name "unconnected-(IC5-THR-Pad6)") (class "Default")
      (node (ref "IC5") (pin "6") (pinfunction "THR_6") (pintype "input"))
    )
    (net (code "69") (name "unconnected-(IC6-DIS-Pad7)") (class "Default")
      (node (ref "IC6") (pin "7") (pinfunction "DIS_7") (pintype "input"))
    )
    (net (code "70") (name "unconnected-(IC6-THR-Pad6)") (class "Default")
      (node (ref "IC6") (pin "6") (pinfunction "THR_6") (pintype "input"))
    )
    (net (code "71") (name "unconnected-(IC7-DIS-Pad7)") (class "Default")
      (node (ref "IC7") (pin "7") (pinfunction "DIS_7") (pintype "input"))
    )
    (net (code "72") (name "unconnected-(IC7-THR-Pad6)") (class "Default")
      (node (ref "IC7") (pin "6") (pinfunction "THR_6") (pintype "input"))
    )
    (net (code "73") (name "unconnected-(IC8-DIS-Pad7)") (class "Default")
      (node (ref "IC8") (pin "7") (pinfunction "DIS_7") (pintype "input"))
    )
    (net (code "74") (name "unconnected-(IC8-THR-Pad6)") (class "Default")
      (node (ref "IC8") (pin "6") (pinfunction "THR_6") (pintype "input"))
    )
    (net (code "75") (name "unconnected-(K1B-O-Pad10)") (class "Default")
      (node (ref "K1") (pin "10") (pinfunction "O_10") (pintype "passive"))
    )
    (net (code "76") (name "unconnected-(M1-A0-PadJ2.12)") (class "Default")
      (node (ref "M1") (pin "J2.12") (pinfunction "A0_J2.12") (pintype "bidirectional"))
    )
    (net (code "77") (name "unconnected-(M1-AREF-PadJ2.13)") (class "Default")
      (node (ref "M1") (pin "J2.13") (pinfunction "AREF_J2.13") (pintype "bidirectional"))
    )
    (net (code "78") (name "unconnected-(M1-D0{slash}RX-PadJ1.2)") (class "Default")
      (node (ref "M1") (pin "J1.2") (pinfunction "D0/RX_J1.2") (pintype "bidirectional"))
    )
    (net (code "79") (name "unconnected-(M1-D1{slash}TX-PadJ1.1)") (class "Default")
      (node (ref "M1") (pin "J1.1") (pinfunction "D1/TX_J1.1") (pintype "bidirectional"))
    )
    (net (code "80") (name "unconnected-(M1-D12{slash}MISO-PadJ1.15)") (class "Default")
      (node (ref "M1") (pin "J1.15") (pinfunction "D12/MISO_J1.15") (pintype "bidirectional"))
    )
    (net (code "81") (name "unconnected-(M1-RST.1-PadJ1.3)") (class "Default")
      (node (ref "M1") (pin "J1.3") (pinfunction "RST.1_J1.3") (pintype "bidirectional"))
    )
    (net (code "82") (name "unconnected-(M1-RST.2-PadJ2.3)") (class "Default")
      (node (ref "M1") (pin "J2.3") (pinfunction "RST.2_J2.3") (pintype "bidirectional"))
    )
    (net (code "83") (name "unconnected-(S2-O-Pad1)") (class "Default")
      (node (ref "S2") (pin "1") (pinfunction "O_1") (pintype "passive"))
    )
    (net (code "84") (name "unconnected-(U$1-PadP$7)") (class "Default")
      (node (ref "U$1") (pin "P$7") (pinfunction "P$7_P$7") (pintype "bidirectional"))
    )
  )
)
